# MCU.net
KiCad netlist of a schematic drawn in Altium Designer
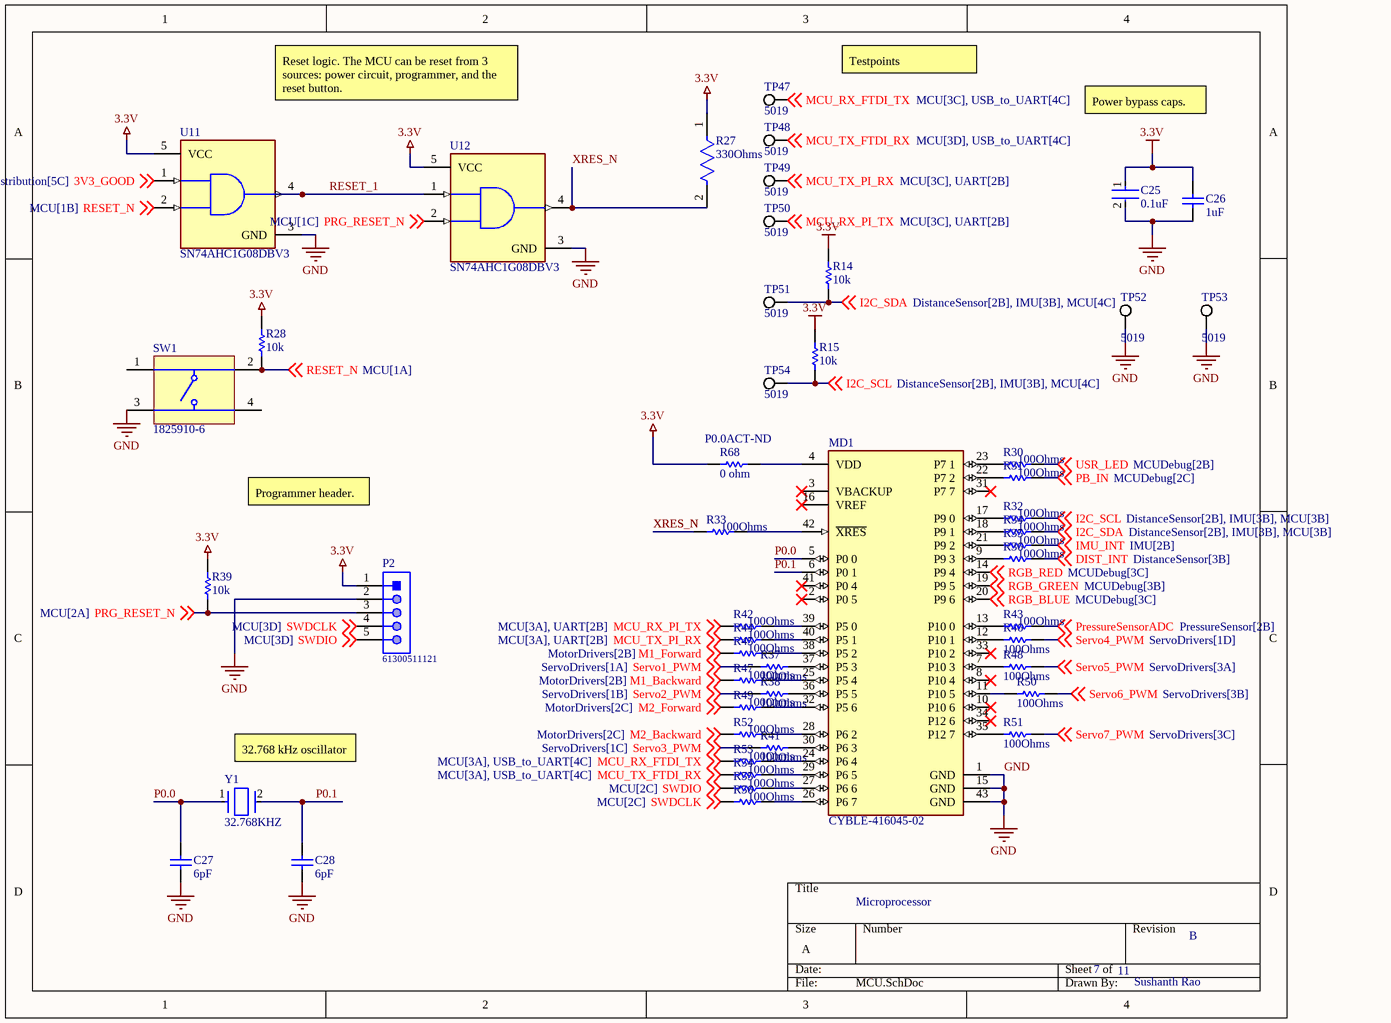
[diagram p0: MCU.SchDoc]

(export (version "E")
  (design (tool "Eeschema 10.0.6"))
  (components
    (comp (ref "C25")
      (value "0.1uF")
      (footprint "FP-CC0805-0_85-MFG")
      (description "CAP CER 0.1UF 25V X7R 0805")
      (fields (field (name "MANUFACTURER PART NUMBER") "CC0805KRX7R8BB104") (field (name "TOLERANCE") "0.1"))
      (libsource (lib "Altium Content Vault") (part "11868f565c42a9108669ba33697ecf6"))
    )
    (comp (ref "C26")
      (value "1uF")
      (footprint "CAPC2013X145X50ML20T25")
      (fields
        (field (name "PART NUMBER") "CC0805ZRY5V8BB105")
        (field (name "MANUFACTURER") "Yageo")
        (field (name "TOLERANCE") "80%")
      )
      (libsource (lib "Altium Content Vault") (part "CAP"))
    )
    (comp (ref "C27")
      (value "6pF")
      (footprint "CAPC2013X94X50LL20T25")
      (fields
        (field (name "MANUFACTURER") "AVX Interconnect / Elco")
        (field (name "PART NUMBER") "08055A6R0CAT2A")
      )
      (libsource (lib "Altium Content Vault") (part "CAP"))
    )
    (comp (ref "C28")
      (value "6pF")
      (footprint "CAPC2013X94X50LL20T25")
      (fields
        (field (name "MANUFACTURER") "AVX Interconnect / Elco")
        (field (name "PART NUMBER") "08055A6R0CAT2A")
      )
      (libsource (lib "Altium Content Vault") (part "CAP"))
    )
    (comp (ref "MD1")
      (value "CYBLE-416045-02")
      (footprint "FP-CYBLE-416045-02-MFG")
      (description "RF TXRX MOD BLUETOOTH TRACE ANT")
      (fields
        (field (name "OCTOPART") "https://octopart.com/cyble-416045-02-cypress+semiconductor-96386825")
        (field (name "MANUFACTURER") "Cypress Semiconductor")
      )
      (libsource (lib "Altium Content Vault") (part "10a29a4e77099fbb6f911efb04878b1"))
    )
    (comp (ref "P2")
      (value "61300511121")
      (footprint "61300511121")
      (description "THT Vertical Pin Header WR-PHD, Pitch 2.54 mm, Single Row, 5 pins")
      (fields (field (name "MANUFACTURER") "Wurth Elektronik") (field (name "PUBLISHER") "WurthElektronik"))
      (libsource (lib "Altium Content Vault") (part "WE-CN-1P-M-R5"))
    )
    (comp (ref "R14")
      (value "10k")
      (footprint "RESC2013X60X35NL10T20")
      (description "Chip Resistor, 10 KOhm, +/- 1%, 0.125 W, -55 to 155 degC, 0805 (2012 Metric), RoHS, Tape and Reel")
      (fields
        (field (name "MANUFACTURER") "Yageo")
        (field (name "MANUFACTURER PART NUMBER") "RC0805FR-0710KL")
      )
      (libsource (lib "Altium Content Vault") (part "RES-2"))
    )
    (comp (ref "R15")
      (value "10k")
      (footprint "RESC2013X60X35NL10T20")
      (description "Chip Resistor, 10 KOhm, +/- 1%, 0.125 W, -55 to 155 degC, 0805 (2012 Metric), RoHS, Tape and Reel")
      (fields
        (field (name "MANUFACTURER") "Yageo")
        (field (name "MANUFACTURER PART NUMBER") "RC0805FR-0710KL")
      )
      (libsource (lib "Altium Content Vault") (part "RES-2"))
    )
    (comp (ref "R27")
      (value "330Ohms")
      (footprint "FP-KTR10-IPC_C")
      (description "Res Thick Film 0805 300Ω 5% 0.125W ±200ppm/°C Automotive Paper T/R")
      (fields (field (name "TOLERANCE") "5%"))
      (libsource (lib "Altium Content Vault") (part "1029c3af85768c4190bb7ad29bc67b5"))
    )
    (comp (ref "R28")
      (value "10k")
      (footprint "RESC2013X60X35NL10T20")
      (description "Chip Resistor, 10 KOhm, +/- 1%, 0.125 W, -55 to 155 degC, 0805 (2012 Metric), RoHS, Tape and Reel")
      (fields
        (field (name "MANUFACTURER") "Yageo")
        (field (name "MANUFACTURER PART NUMBER") "RC0805FR-0710KL")
      )
      (libsource (lib "Altium Content Vault") (part "RES-2"))
    )
    (comp (ref "R30")
      (value "100Ohms")
      (footprint "RESC2013X60X35ML10T20")
      (description "Chip Resistor, 100 Ohm, +/-1%, 0.125 W, -55 to 155 degC, 0805 (2012 Metric), RoHS, Tape and Reel")
      (fields (field (name "TOLERANCE") "1%") (field (name "MANUFACTURER") "Yageo"))
      (libsource (lib "Altium Content Vault") (part "RES-2"))
    )
    (comp (ref "R31")
      (value "100Ohms")
      (footprint "RESC2013X60X35ML10T20")
      (description "Chip Resistor, 100 Ohm, +/-1%, 0.125 W, -55 to 155 degC, 0805 (2012 Metric), RoHS, Tape and Reel")
      (fields (field (name "TOLERANCE") "1%") (field (name "MANUFACTURER") "Yageo"))
      (libsource (lib "Altium Content Vault") (part "RES-2"))
    )
    (comp (ref "R32")
      (value "100Ohms")
      (footprint "RESC2013X60X35ML10T20")
      (description "Chip Resistor, 100 Ohm, +/-1%, 0.125 W, -55 to 155 degC, 0805 (2012 Metric), RoHS, Tape and Reel")
      (fields (field (name "TOLERANCE") "1%") (field (name "MANUFACTURER") "Yageo"))
      (libsource (lib "Altium Content Vault") (part "RES-2"))
    )
    (comp (ref "R33")
      (value "100Ohms")
      (footprint "RESC2013X60X35ML10T20")
      (description "Chip Resistor, 100 Ohm, +/-1%, 0.125 W, -55 to 155 degC, 0805 (2012 Metric), RoHS, Tape and Reel")
      (fields (field (name "TOLERANCE") "1%") (field (name "MANUFACTURER") "Yageo"))
      (libsource (lib "Altium Content Vault") (part "RES-2"))
    )
    (comp (ref "R34")
      (value "100Ohms")
      (footprint "RESC2013X60X35ML10T20")
      (description "Chip Resistor, 100 Ohm, +/-1%, 0.125 W, -55 to 155 degC, 0805 (2012 Metric), RoHS, Tape and Reel")
      (fields (field (name "TOLERANCE") "1%") (field (name "MANUFACTURER") "Yageo"))
      (libsource (lib "Altium Content Vault") (part "RES-2"))
    )
    (comp (ref "R35")
      (value "100Ohms")
      (footprint "RESC2013X60X35ML10T20")
      (description "Chip Resistor, 100 Ohm, +/-1%, 0.125 W, -55 to 155 degC, 0805 (2012 Metric), RoHS, Tape and Reel")
      (fields (field (name "TOLERANCE") "1%") (field (name "MANUFACTURER") "Yageo"))
      (libsource (lib "Altium Content Vault") (part "RES-2"))
    )
    (comp (ref "R36")
      (value "100Ohms")
      (footprint "RESC2013X60X35ML10T20")
      (description "Chip Resistor, 100 Ohm, +/-1%, 0.125 W, -55 to 155 degC, 0805 (2012 Metric), RoHS, Tape and Reel")
      (fields (field (name "TOLERANCE") "1%") (field (name "MANUFACTURER") "Yageo"))
      (libsource (lib "Altium Content Vault") (part "RES-2"))
    )
    (comp (ref "R37")
      (value "100Ohms")
      (footprint "RESC2013X60X35ML10T20")
      (description "Chip Resistor, 100 Ohm, +/-1%, 0.125 W, -55 to 155 degC, 0805 (2012 Metric), RoHS, Tape and Reel")
      (fields (field (name "TOLERANCE") "1%") (field (name "MANUFACTURER") "Yageo"))
      (libsource (lib "Altium Content Vault") (part "RES-2"))
    )
    (comp (ref "R38")
      (value "100Ohms")
      (footprint "RESC2013X60X35ML10T20")
      (description "Chip Resistor, 100 Ohm, +/-1%, 0.125 W, -55 to 155 degC, 0805 (2012 Metric), RoHS, Tape and Reel")
      (fields (field (name "TOLERANCE") "1%") (field (name "MANUFACTURER") "Yageo"))
      (libsource (lib "Altium Content Vault") (part "RES-2"))
    )
    (comp (ref "R39")
      (value "10k")
      (footprint "RESC2013X60X35NL10T20")
      (description "Chip Resistor, 10 KOhm, +/- 1%, 0.125 W, -55 to 155 degC, 0805 (2012 Metric), RoHS, Tape and Reel")
      (fields
        (field (name "MANUFACTURER") "Yageo")
        (field (name "MANUFACTURER PART NUMBER") "RC0805FR-0710KL")
      )
      (libsource (lib "Altium Content Vault") (part "RES-2"))
    )
    (comp (ref "R41")
      (value "100Ohms")
      (footprint "RESC2013X60X35ML10T20")
      (description "Chip Resistor, 100 Ohm, +/-1%, 0.125 W, -55 to 155 degC, 0805 (2012 Metric), RoHS, Tape and Reel")
      (fields (field (name "TOLERANCE") "1%") (field (name "MANUFACTURER") "Yageo"))
      (libsource (lib "Altium Content Vault") (part "RES-2"))
    )
    (comp (ref "R42")
      (value "100Ohms")
      (footprint "RESC2013X60X35ML10T20")
      (description "Chip Resistor, 100 Ohm, +/-1%, 0.125 W, -55 to 155 degC, 0805 (2012 Metric), RoHS, Tape and Reel")
      (fields (field (name "TOLERANCE") "1%") (field (name "MANUFACTURER") "Yageo"))
      (libsource (lib "Altium Content Vault") (part "RES-2"))
    )
    (comp (ref "R43")
      (value "100Ohms")
      (footprint "RESC2013X60X35ML10T20")
      (description "Chip Resistor, 100 Ohm, +/-1%, 0.125 W, -55 to 155 degC, 0805 (2012 Metric), RoHS, Tape and Reel")
      (fields (field (name "TOLERANCE") "1%") (field (name "MANUFACTURER") "Yageo"))
      (libsource (lib "Altium Content Vault") (part "RES-2"))
    )
    (comp (ref "R44")
      (value "100Ohms")
      (footprint "RESC2013X60X35ML10T20")
      (description "Chip Resistor, 100 Ohm, +/-1%, 0.125 W, -55 to 155 degC, 0805 (2012 Metric), RoHS, Tape and Reel")
      (fields (field (name "TOLERANCE") "1%") (field (name "MANUFACTURER") "Yageo"))
      (libsource (lib "Altium Content Vault") (part "RES-2"))
    )
    (comp (ref "R45")
      (value "100Ohms")
      (footprint "RESC2013X60X35ML10T20")
      (description "Chip Resistor, 100 Ohm, +/-1%, 0.125 W, -55 to 155 degC, 0805 (2012 Metric), RoHS, Tape and Reel")
      (fields (field (name "TOLERANCE") "1%") (field (name "MANUFACTURER") "Yageo"))
      (libsource (lib "Altium Content Vault") (part "RES-2"))
    )
    (comp (ref "R46")
      (value "100Ohms")
      (footprint "RESC2013X60X35ML10T20")
      (description "Chip Resistor, 100 Ohm, +/-1%, 0.125 W, -55 to 155 degC, 0805 (2012 Metric), RoHS, Tape and Reel")
      (fields (field (name "TOLERANCE") "1%") (field (name "MANUFACTURER") "Yageo"))
      (libsource (lib "Altium Content Vault") (part "RES-2"))
    )
    (comp (ref "R47")
      (value "100Ohms")
      (footprint "RESC2013X60X35ML10T20")
      (description "Chip Resistor, 100 Ohm, +/-1%, 0.125 W, -55 to 155 degC, 0805 (2012 Metric), RoHS, Tape and Reel")
      (fields (field (name "TOLERANCE") "1%") (field (name "MANUFACTURER") "Yageo"))
      (libsource (lib "Altium Content Vault") (part "RES-2"))
    )
    (comp (ref "R48")
      (value "100Ohms")
      (footprint "RESC2013X60X35ML10T20")
      (description "Chip Resistor, 100 Ohm, +/-1%, 0.125 W, -55 to 155 degC, 0805 (2012 Metric), RoHS, Tape and Reel")
      (fields (field (name "TOLERANCE") "1%") (field (name "MANUFACTURER") "Yageo"))
      (libsource (lib "Altium Content Vault") (part "RES-2"))
    )
    (comp (ref "R49")
      (value "100Ohms")
      (footprint "RESC2013X60X35ML10T20")
      (description "Chip Resistor, 100 Ohm, +/-1%, 0.125 W, -55 to 155 degC, 0805 (2012 Metric), RoHS, Tape and Reel")
      (fields (field (name "TOLERANCE") "1%") (field (name "MANUFACTURER") "Yageo"))
      (libsource (lib "Altium Content Vault") (part "RES-2"))
    )
    (comp (ref "R50")
      (value "100Ohms")
      (footprint "RESC2013X60X35ML10T20")
      (description "Chip Resistor, 100 Ohm, +/-1%, 0.125 W, -55 to 155 degC, 0805 (2012 Metric), RoHS, Tape and Reel")
      (fields (field (name "TOLERANCE") "1%") (field (name "MANUFACTURER") "Yageo"))
      (libsource (lib "Altium Content Vault") (part "RES-2"))
    )
    (comp (ref "R51")
      (value "100Ohms")
      (footprint "RESC2013X60X35ML10T20")
      (description "Chip Resistor, 100 Ohm, +/-1%, 0.125 W, -55 to 155 degC, 0805 (2012 Metric), RoHS, Tape and Reel")
      (fields (field (name "TOLERANCE") "1%") (field (name "MANUFACTURER") "Yageo"))
      (libsource (lib "Altium Content Vault") (part "RES-2"))
    )
    (comp (ref "R52")
      (value "100Ohms")
      (footprint "RESC2013X60X35ML10T20")
      (description "Chip Resistor, 100 Ohm, +/-1%, 0.125 W, -55 to 155 degC, 0805 (2012 Metric), RoHS, Tape and Reel")
      (fields (field (name "TOLERANCE") "1%") (field (name "MANUFACTURER") "Yageo"))
      (libsource (lib "Altium Content Vault") (part "RES-2"))
    )
    (comp (ref "R53")
      (value "100Ohms")
      (footprint "RESC2013X60X35ML10T20")
      (description "Chip Resistor, 100 Ohm, +/-1%, 0.125 W, -55 to 155 degC, 0805 (2012 Metric), RoHS, Tape and Reel")
      (fields (field (name "TOLERANCE") "1%") (field (name "MANUFACTURER") "Yageo"))
      (libsource (lib "Altium Content Vault") (part "RES-2"))
    )
    (comp (ref "R54")
      (value "100Ohms")
      (footprint "RESC2013X60X35ML10T20")
      (description "Chip Resistor, 100 Ohm, +/-1%, 0.125 W, -55 to 155 degC, 0805 (2012 Metric), RoHS, Tape and Reel")
      (fields (field (name "TOLERANCE") "1%") (field (name "MANUFACTURER") "Yageo"))
      (libsource (lib "Altium Content Vault") (part "RES-2"))
    )
    (comp (ref "R55")
      (value "100Ohms")
      (footprint "RESC2013X60X35ML10T20")
      (description "Chip Resistor, 100 Ohm, +/-1%, 0.125 W, -55 to 155 degC, 0805 (2012 Metric), RoHS, Tape and Reel")
      (fields (field (name "TOLERANCE") "1%") (field (name "MANUFACTURER") "Yageo"))
      (libsource (lib "Altium Content Vault") (part "RES-2"))
    )
    (comp (ref "R56")
      (value "100Ohms")
      (footprint "RESC2013X60X35ML10T20")
      (description "Chip Resistor, 100 Ohm, +/-1%, 0.125 W, -55 to 155 degC, 0805 (2012 Metric), RoHS, Tape and Reel")
      (fields (field (name "TOLERANCE") "1%") (field (name "MANUFACTURER") "Yageo"))
      (libsource (lib "Altium Content Vault") (part "RES-2"))
    )
    (comp (ref "R68")
      (value "0 ohm")
      (footprint "RESC2013X70X40NL20T20")
      (description "Chip Resistor, 0 Ohm, +/- 1%, 0.125 W, -55 to 155 degC, 0805 (2012 Metric), RoHS, Tape and Reel")
      (fields
        (field (name "PARTNUMBER") "ERJ-6GEY0R00V")
        (field (name "TOLERANCE") "5%")
        (field (name "SUPPLIER PART NUMBER 1") "P0.0ACT-ND")
      )
      (libsource (lib "Altium Content Vault") (part "RES-2"))
    )
    (comp (ref "SW1")
      (value "1825910-6")
      (footprint "TECO-1825910-6_V")
      (description "Tact Switch, SPST-NO, 0.05 A, -35 to 85 degC, 4-Pin THD, RoHS, Bulk")
      (fields (field (name "MANUFACTURER") "TE Connectivity"))
      (libsource (lib "Altium Content Vault") (part "SW-SPST-4_A"))
    )
    (comp (ref "TP47")
      (value "5019")
      (footprint "KSTN-5019_V")
      (description "Test Point, 1 Position SMD, RoHS, Tape and Reel")
      (fields (field (name "MANUFACTURER") "Keystone Electronics"))
      (libsource (lib "Altium Content Vault") (part "TESTPOINT_WHITE"))
    )
    (comp (ref "TP48")
      (value "5019")
      (footprint "KSTN-5019_V")
      (description "Test Point, 1 Position SMD, RoHS, Tape and Reel")
      (fields (field (name "MANUFACTURER") "Keystone Electronics"))
      (libsource (lib "Altium Content Vault") (part "TESTPOINT_WHITE"))
    )
    (comp (ref "TP49")
      (value "5019")
      (footprint "KSTN-5019_V")
      (description "Test Point, 1 Position SMD, RoHS, Tape and Reel")
      (fields (field (name "MANUFACTURER") "Keystone Electronics"))
      (libsource (lib "Altium Content Vault") (part "TESTPOINT_WHITE"))
    )
    (comp (ref "TP50")
      (value "5019")
      (footprint "KSTN-5019_V")
      (description "Test Point, 1 Position SMD, RoHS, Tape and Reel")
      (fields (field (name "MANUFACTURER") "Keystone Electronics"))
      (libsource (lib "Altium Content Vault") (part "TESTPOINT_WHITE"))
    )
    (comp (ref "TP51")
      (value "5019")
      (footprint "KSTN-5019_V")
      (description "Test Point, 1 Position SMD, RoHS, Tape and Reel")
      (fields (field (name "MANUFACTURER") "Keystone Electronics"))
      (libsource (lib "Altium Content Vault") (part "TESTPOINT_WHITE"))
    )
    (comp (ref "TP52")
      (value "5019")
      (footprint "KSTN-5019_V")
      (description "Test Point, 1 Position SMD, RoHS, Tape and Reel")
      (fields (field (name "MANUFACTURER") "Keystone Electronics"))
      (libsource (lib "Altium Content Vault") (part "TESTPOINT_WHITE"))
    )
    (comp (ref "TP53")
      (value "5019")
      (footprint "KSTN-5019_V")
      (description "Test Point, 1 Position SMD, RoHS, Tape and Reel")
      (fields (field (name "MANUFACTURER") "Keystone Electronics"))
      (libsource (lib "Altium Content Vault") (part "TESTPOINT_WHITE"))
    )
    (comp (ref "TP54")
      (value "5019")
      (footprint "KSTN-5019_V")
      (description "Test Point, 1 Position SMD, RoHS, Tape and Reel")
      (fields (field (name "MANUFACTURER") "Keystone Electronics"))
      (libsource (lib "Altium Content Vault") (part "TESTPOINT_WHITE"))
    )
    (comp (ref "U11")
      (value "SN74AHC1G08DBV3")
      (footprint "FP-DBV0005A-IPC_C")
      (description "IC GATE AND 1CH 2-INP SOT23-5")
      (libsource (lib "Altium Content Vault") (part "675e79b427d6219a5295bf943425e1c"))
    )
    (comp (ref "U12")
      (value "SN74AHC1G08DBV3")
      (footprint "FP-DBV0005A-IPC_C")
      (description "IC GATE AND 1CH 2-INP SOT23-5")
      (libsource (lib "Altium Content Vault") (part "675e79b427d6219a5295bf943425e1c"))
    )
    (comp (ref "Y1")
      (value "32.768KHZ")
      (footprint "FP-ABS07-120-MFG")
      (description "CRYSTAL 32.7680KHZ 6PF SMD")
      (fields (field (name "TOLERANCE") "20ppm"))
      (libsource (lib "Altium Content Vault") (part "c23a69dc6c9e2f18f2079038eb95dd1"))
    )
  )
  (nets
    (net (code "1") (name "/P0.0") (class "Default")
      (node (ref "C27") (pin "2") (pinfunction "2_2") (pintype "passive"))
      (node (ref "MD1") (pin "5") (pinfunction "P0_0_5") (pintype "bidirectional"))
      (node (ref "Y1") (pin "1") (pinfunction "1_1") (pintype "passive"))
    )
    (net (code "2") (name "/P0.1") (class "Default")
      (node (ref "C28") (pin "2") (pinfunction "2_2") (pintype "passive"))
      (node (ref "MD1") (pin "6") (pinfunction "P0_1_6") (pintype "bidirectional"))
      (node (ref "Y1") (pin "2") (pinfunction "2_2") (pintype "passive"))
    )
    (net (code "3") (name "/RESET_1") (class "Default")
      (node (ref "U11") (pin "4") (pinfunction "Y_4") (pintype "output"))
      (node (ref "U12") (pin "1") (pinfunction "A_1") (pintype "input"))
    )
    (net (code "4") (name "/XRES_N") (class "Default")
      (node (ref "R27") (pin "2") (pinfunction "2_2") (pintype "passive"))
      (node (ref "R33") (pin "1") (pinfunction "1_1") (pintype "passive"))
      (node (ref "U12") (pin "4") (pinfunction "Y_4") (pintype "output"))
    )
    (net (code "5") (name "3.3V") (class "Default")
      (node (ref "C25") (pin "1") (pinfunction "1_1") (pintype "passive"))
      (node (ref "C26") (pin "2") (pinfunction "2_2") (pintype "passive"))
      (node (ref "P2") (pin "1") (pinfunction "1_1") (pintype "passive"))
      (node (ref "R14") (pin "2") (pinfunction "2_2") (pintype "passive"))
      (node (ref "R15") (pin "2") (pinfunction "2_2") (pintype "passive"))
      (node (ref "R27") (pin "1") (pinfunction "1_1") (pintype "passive"))
      (node (ref "R28") (pin "2") (pinfunction "2_2") (pintype "passive"))
      (node (ref "R39") (pin "2") (pinfunction "2_2") (pintype "passive"))
      (node (ref "R68") (pin "1") (pinfunction "1_1") (pintype "passive"))
      (node (ref "U11") (pin "5") (pinfunction "VCC_5") (pintype "power_in"))
      (node (ref "U12") (pin "5") (pinfunction "VCC_5") (pintype "power_in"))
    )
    (net (code "6") (name "3V3_GOOD") (class "Default")
      (node (ref "U11") (pin "1") (pinfunction "A_1") (pintype "input"))
    )
    (net (code "7") (name "DIST_INT") (class "Default")
      (node (ref "R36") (pin "2") (pinfunction "2_2") (pintype "passive"))
    )
    (net (code "8") (name "GND") (class "Default")
      (node (ref "C25") (pin "2") (pinfunction "2_2") (pintype "passive"))
      (node (ref "C26") (pin "1") (pinfunction "1_1") (pintype "passive"))
      (node (ref "C27") (pin "1") (pinfunction "1_1") (pintype "passive"))
      (node (ref "C28") (pin "1") (pinfunction "1_1") (pintype "passive"))
      (node (ref "MD1") (pin "1") (pinfunction "GND_1") (pintype "power_in"))
      (node (ref "MD1") (pin "15") (pinfunction "GND_15") (pintype "power_in"))
      (node (ref "MD1") (pin "43") (pinfunction "GND_43") (pintype "power_in"))
      (node (ref "P2") (pin "2") (pinfunction "2_2") (pintype "passive"))
      (node (ref "SW1") (pin "3") (pinfunction "3_3") (pintype "passive"))
      (node (ref "TP52") (pin "1") (pinfunction "1_1") (pintype "passive"))
      (node (ref "TP53") (pin "1") (pinfunction "1_1") (pintype "passive"))
      (node (ref "U11") (pin "3") (pinfunction "GND_3") (pintype "power_in"))
      (node (ref "U12") (pin "3") (pinfunction "GND_3") (pintype "power_in"))
    )
    (net (code "9") (name "I2C_SCL") (class "Default")
      (node (ref "R15") (pin "1") (pinfunction "1_1") (pintype "passive"))
      (node (ref "R32") (pin "2") (pinfunction "2_2") (pintype "passive"))
      (node (ref "TP54") (pin "1") (pinfunction "1_1") (pintype "passive"))
    )
    (net (code "10") (name "I2C_SDA") (class "Default")
      (node (ref "R14") (pin "1") (pinfunction "1_1") (pintype "passive"))
      (node (ref "R34") (pin "2") (pinfunction "2_2") (pintype "passive"))
      (node (ref "TP51") (pin "1") (pinfunction "1_1") (pintype "passive"))
    )
    (net (code "11") (name "IMU_INT") (class "Default")
      (node (ref "R35") (pin "2") (pinfunction "2_2") (pintype "passive"))
    )
    (net (code "12") (name "M1_Backward") (class "Default")
      (node (ref "R47") (pin "1") (pinfunction "1_1") (pintype "passive"))
    )
    (net (code "13") (name "M1_Forward") (class "Default")
      (node (ref "R45") (pin "1") (pinfunction "1_1") (pintype "passive"))
    )
    (net (code "14") (name "M2_Backward") (class "Default")
      (node (ref "R52") (pin "1") (pinfunction "1_1") (pintype "passive"))
    )
    (net (code "15") (name "M2_Forward") (class "Default")
      (node (ref "R49") (pin "1") (pinfunction "1_1") (pintype "passive"))
    )
    (net (code "16") (name "MCU_RX_FTDI_TX") (class "Default")
      (node (ref "R53") (pin "1") (pinfunction "1_1") (pintype "passive"))
      (node (ref "TP47") (pin "1") (pinfunction "1_1") (pintype "passive"))
    )
    (net (code "17") (name "MCU_RX_PI_TX") (class "Default")
      (node (ref "R42") (pin "1") (pinfunction "1_1") (pintype "passive"))
      (node (ref "TP50") (pin "1") (pinfunction "1_1") (pintype "passive"))
    )
    (net (code "18") (name "MCU_TX_FTDI_RX") (class "Default")
      (node (ref "R54") (pin "1") (pinfunction "1_1") (pintype "passive"))
      (node (ref "TP48") (pin "1") (pinfunction "1_1") (pintype "passive"))
    )
    (net (code "19") (name "MCU_TX_PI_RX") (class "Default")
      (node (ref "R44") (pin "1") (pinfunction "1_1") (pintype "passive"))
      (node (ref "TP49") (pin "1") (pinfunction "1_1") (pintype "passive"))
    )
    (net (code "20") (name "Net-(MD1-P5_0)") (class "Default")
      (node (ref "MD1") (pin "39") (pinfunction "P5_0_39") (pintype "bidirectional"))
      (node (ref "R42") (pin "2") (pinfunction "2_2") (pintype "passive"))
    )
    (net (code "21") (name "Net-(MD1-P5_1)") (class "Default")
      (node (ref "MD1") (pin "40") (pinfunction "P5_1_40") (pintype "bidirectional"))
      (node (ref "R44") (pin "2") (pinfunction "2_2") (pintype "passive"))
    )
    (net (code "22") (name "Net-(MD1-P5_2)") (class "Default")
      (node (ref "MD1") (pin "38") (pinfunction "P5_2_38") (pintype "bidirectional"))
      (node (ref "R45") (pin "2") (pinfunction "2_2") (pintype "passive"))
    )
    (net (code "23") (name "Net-(MD1-P5_3)") (class "Default")
      (node (ref "MD1") (pin "37") (pinfunction "P5_3_37") (pintype "bidirectional"))
      (node (ref "R37") (pin "1") (pinfunction "1_1") (pintype "passive"))
    )
    (net (code "24") (name "Net-(MD1-P5_4)") (class "Default")
      (node (ref "MD1") (pin "25") (pinfunction "P5_4_25") (pintype "bidirectional"))
      (node (ref "R47") (pin "2") (pinfunction "2_2") (pintype "passive"))
    )
    (net (code "25") (name "Net-(MD1-P5_5)") (class "Default")
      (node (ref "MD1") (pin "36") (pinfunction "P5_5_36") (pintype "bidirectional"))
      (node (ref "R38") (pin "1") (pinfunction "1_1") (pintype "passive"))
    )
    (net (code "26") (name "Net-(MD1-P5_6)") (class "Default")
      (node (ref "MD1") (pin "32") (pinfunction "P5_6_32") (pintype "bidirectional"))
      (node (ref "R49") (pin "2") (pinfunction "2_2") (pintype "passive"))
    )
    (net (code "27") (name "Net-(MD1-P6_2)") (class "Default")
      (node (ref "MD1") (pin "28") (pinfunction "P6_2_28") (pintype "bidirectional"))
      (node (ref "R52") (pin "2") (pinfunction "2_2") (pintype "passive"))
    )
    (net (code "28") (name "Net-(MD1-P6_3)") (class "Default")
      (node (ref "MD1") (pin "30") (pinfunction "P6_3_30") (pintype "bidirectional"))
      (node (ref "R41") (pin "1") (pinfunction "1_1") (pintype "passive"))
    )
    (net (code "29") (name "Net-(MD1-P6_4)") (class "Default")
      (node (ref "MD1") (pin "24") (pinfunction "P6_4_24") (pintype "bidirectional"))
      (node (ref "R53") (pin "2") (pinfunction "2_2") (pintype "passive"))
    )
    (net (code "30") (name "Net-(MD1-P6_5)") (class "Default")
      (node (ref "MD1") (pin "29") (pinfunction "P6_5_29") (pintype "bidirectional"))
      (node (ref "R54") (pin "2") (pinfunction "2_2") (pintype "passive"))
    )
    (net (code "31") (name "Net-(MD1-P6_6)") (class "Default")
      (node (ref "MD1") (pin "27") (pinfunction "P6_6_27") (pintype "bidirectional"))
      (node (ref "R55") (pin "2") (pinfunction "2_2") (pintype "passive"))
    )
    (net (code "32") (name "Net-(MD1-P6_7)") (class "Default")
      (node (ref "MD1") (pin "26") (pinfunction "P6_7_26") (pintype "bidirectional"))
      (node (ref "R56") (pin "2") (pinfunction "2_2") (pintype "passive"))
    )
    (net (code "33") (name "Net-(MD1-P7_1)") (class "Default")
      (node (ref "MD1") (pin "23") (pinfunction "P7_1_23") (pintype "bidirectional"))
      (node (ref "R30") (pin "1") (pinfunction "1_1") (pintype "passive"))
    )
    (net (code "34") (name "Net-(MD1-P7_2)") (class "Default")
      (node (ref "MD1") (pin "22") (pinfunction "P7_2_22") (pintype "bidirectional"))
      (node (ref "R31") (pin "1") (pinfunction "1_1") (pintype "passive"))
    )
    (net (code "35") (name "Net-(MD1-P9_0)") (class "Default")
      (node (ref "MD1") (pin "17") (pinfunction "P9_0_17") (pintype "bidirectional"))
      (node (ref "R32") (pin "1") (pinfunction "1_1") (pintype "passive"))
    )
    (net (code "36") (name "Net-(MD1-P9_1)") (class "Default")
      (node (ref "MD1") (pin "18") (pinfunction "P9_1_18") (pintype "bidirectional"))
      (node (ref "R34") (pin "1") (pinfunction "1_1") (pintype "passive"))
    )
    (net (code "37") (name "Net-(MD1-P9_2)") (class "Default")
      (node (ref "MD1") (pin "21") (pinfunction "P9_2_21") (pintype "bidirectional"))
      (node (ref "R35") (pin "1") (pinfunction "1_1") (pintype "passive"))
    )
    (net (code "38") (name "Net-(MD1-P9_3)") (class "Default")
      (node (ref "MD1") (pin "9") (pinfunction "P9_3_9") (pintype "bidirectional"))
      (node (ref "R36") (pin "1") (pinfunction "1_1") (pintype "passive"))
    )
    (net (code "39") (name "Net-(MD1-P10_0)") (class "Default")
      (node (ref "MD1") (pin "13") (pinfunction "P10_0_13") (pintype "bidirectional"))
      (node (ref "R43") (pin "1") (pinfunction "1_1") (pintype "passive"))
    )
    (net (code "40") (name "Net-(MD1-P10_1)") (class "Default")
      (node (ref "MD1") (pin "12") (pinfunction "P10_1_12") (pintype "bidirectional"))
      (node (ref "R46") (pin "1") (pinfunction "1_1") (pintype "passive"))
    )
    (net (code "41") (name "Net-(MD1-P10_3)") (class "Default")
      (node (ref "MD1") (pin "7") (pinfunction "P10_3_7") (pintype "bidirectional"))
      (node (ref "R48") (pin "1") (pinfunction "1_1") (pintype "passive"))
    )
    (net (code "42") (name "Net-(MD1-P10_5)") (class "Default")
      (node (ref "MD1") (pin "11") (pinfunction "P10_5_11") (pintype "bidirectional"))
      (node (ref "R50") (pin "1") (pinfunction "1_1") (pintype "passive"))
    )
    (net (code "43") (name "Net-(MD1-P12_7)") (class "Default")
      (node (ref "MD1") (pin "35") (pinfunction "P12_7_35") (pintype "bidirectional"))
      (node (ref "R51") (pin "2") (pinfunction "2_2") (pintype "passive"))
    )
    (net (code "44") (name "Net-(MD1-VDD)") (class "Default")
      (node (ref "MD1") (pin "4") (pinfunction "VDD_4") (pintype "power_in"))
      (node (ref "R68") (pin "2") (pinfunction "2_2") (pintype "passive"))
    )
    (net (code "45") (name "Net-(MD1-~{XRES})") (class "Default")
      (node (ref "MD1") (pin "42") (pinfunction "~{XRES}_42") (pintype "input"))
      (node (ref "R33") (pin "2") (pinfunction "2_2") (pintype "passive"))
    )
    (net (code "46") (name "PB_IN") (class "Default")
      (node (ref "R31") (pin "2") (pinfunction "2_2") (pintype "passive"))
    )
    (net (code "47") (name "PRG_RESET_N") (class "Default")
      (node (ref "P2") (pin "3") (pinfunction "3_3") (pintype "passive"))
      (node (ref "R39") (pin "1") (pinfunction "1_1") (pintype "passive"))
      (node (ref "U12") (pin "2") (pinfunction "B_2") (pintype "input"))
    )
    (net (code "48") (name "PressureSensorADC") (class "Default")
      (node (ref "R43") (pin "2") (pinfunction "2_2") (pintype "passive"))
    )
    (net (code "49") (name "RESET_N") (class "Default")
      (node (ref "R28") (pin "1") (pinfunction "1_1") (pintype "passive"))
      (node (ref "SW1") (pin "2") (pinfunction "2_2") (pintype "passive"))
      (node (ref "U11") (pin "2") (pinfunction "B_2") (pintype "input"))
    )
    (net (code "50") (name "RGB_BLUE") (class "Default")
      (node (ref "MD1") (pin "20") (pinfunction "P9_6_20") (pintype "bidirectional"))
    )
    (net (code "51") (name "RGB_GREEN") (class "Default")
      (node (ref "MD1") (pin "19") (pinfunction "P9_5_19") (pintype "bidirectional"))
    )
    (net (code "52") (name "RGB_RED") (class "Default")
      (node (ref "MD1") (pin "14") (pinfunction "P9_4_14") (pintype "bidirectional"))
    )
    (net (code "53") (name "SWDCLK") (class "Default")
      (node (ref "P2") (pin "4") (pinfunction "4_4") (pintype "passive"))
      (node (ref "R56") (pin "1") (pinfunction "1_1") (pintype "passive"))
    )
    (net (code "54") (name "SWDIO") (class "Default")
      (node (ref "P2") (pin "5") (pinfunction "5_5") (pintype "passive"))
      (node (ref "R55") (pin "1") (pinfunction "1_1") (pintype "passive"))
    )
    (net (code "55") (name "Servo1_PWM") (class "Default")
      (node (ref "R37") (pin "2") (pinfunction "2_2") (pintype "passive"))
    )
    (net (code "56") (name "Servo2_PWM") (class "Default")
      (node (ref "R38") (pin "2") (pinfunction "2_2") (pintype "passive"))
    )
    (net (code "57") (name "Servo3_PWM") (class "Default")
      (node (ref "R41") (pin "2") (pinfunction "2_2") (pintype "passive"))
    )
    (net (code "58") (name "Servo4_PWM") (class "Default")
      (node (ref "R46") (pin "2") (pinfunction "2_2") (pintype "passive"))
    )
    (net (code "59") (name "Servo5_PWM") (class "Default")
      (node (ref "R48") (pin "2") (pinfunction "2_2") (pintype "passive"))
    )
    (net (code "60") (name "Servo6_PWM") (class "Default")
      (node (ref "R50") (pin "2") (pinfunction "2_2") (pintype "passive"))
    )
    (net (code "61") (name "Servo7_PWM") (class "Default")
      (node (ref "R51") (pin "1") (pinfunction "1_1") (pintype "passive"))
    )
    (net (code "62") (name "USR_LED") (class "Default")
      (node (ref "R30") (pin "2") (pinfunction "2_2") (pintype "passive"))
    )
    (net (code "63") (name "unconnected-(MD1-P0_4-Pad41)") (class "Default")
      (node (ref "MD1") (pin "41") (pinfunction "P0_4_41") (pintype "bidirectional+no_connect"))
    )
    (net (code "64") (name "unconnected-(MD1-P0_5-Pad2)") (class "Default")
      (node (ref "MD1") (pin "2") (pinfunction "P0_5_2") (pintype "bidirectional+no_connect"))
    )
    (net (code "65") (name "unconnected-(MD1-P7_7-Pad31)") (class "Default")
      (node (ref "MD1") (pin "31") (pinfunction "P7_7_31") (pintype "bidirectional+no_connect"))
    )
    (net (code "66") (name "unconnected-(MD1-P10_2-Pad33)") (class "Default")
      (node (ref "MD1") (pin "33") (pinfunction "P10_2_33") (pintype "bidirectional+no_connect"))
    )
    (net (code "67") (name "unconnected-(MD1-P10_4-Pad8)") (class "Default")
      (node (ref "MD1") (pin "8") (pinfunction "P10_4_8") (pintype "bidirectional+no_connect"))
    )
    (net (code "68") (name "unconnected-(MD1-P10_6-Pad10)") (class "Default")
      (node (ref "MD1") (pin "10") (pinfunction "P10_6_10") (pintype "bidirectional+no_connect"))
    )
    (net (code "69") (name "unconnected-(MD1-P12_6-Pad34)") (class "Default")
      (node (ref "MD1") (pin "34") (pinfunction "P12_6_34") (pintype "bidirectional+no_connect"))
    )
    (net (code "70") (name "unconnected-(MD1-VBACKUP-Pad3)") (class "Default")
      (node (ref "MD1") (pin "3") (pinfunction "VBACKUP_3") (pintype "power_in+no_connect"))
    )
    (net (code "71") (name "unconnected-(MD1-VREF-Pad16)") (class "Default")
      (node (ref "MD1") (pin "16") (pinfunction "VREF_16") (pintype "power_in+no_connect"))
    )
    (net (code "72") (name "unconnected-(SW1-Pad1)") (class "Default")
      (node (ref "SW1") (pin "1") (pinfunction "1_1") (pintype "passive"))
    )
    (net (code "73") (name "unconnected-(SW1-Pad4)") (class "Default")
      (node (ref "SW1") (pin "4") (pinfunction "4_4") (pintype "passive"))
    )
  )
)
